# fixed.net
KiCad netlist of a schematic drawn in EAGLE
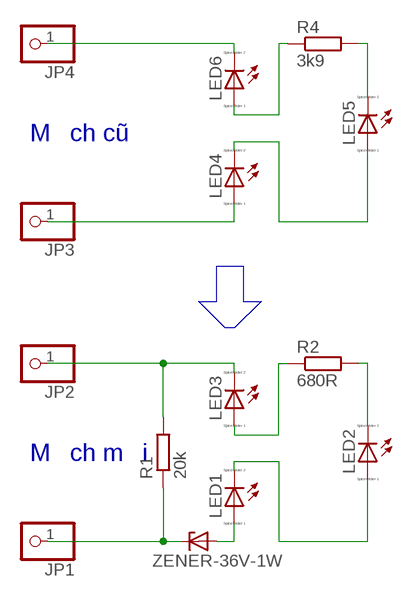
[diagram p0: schematic, sheet 1]

(export (version "E")
  (design (tool "Eeschema 10.0.6"))
  (components
    (comp (ref "JP1")
      (value "PINHD-1X1")
      (footprint "eagle-import:1X01")
      (libsource (lib "eagle-import") (part "PINHD-1X1"))
    )
    (comp (ref "JP2")
      (value "PINHD-1X1")
      (footprint "eagle-import:1X01")
      (libsource (lib "eagle-import") (part "PINHD-1X1"))
    )
    (comp (ref "JP3")
      (value "PINHD-1X1")
      (footprint "eagle-import:1X01")
      (libsource (lib "eagle-import") (part "PINHD-1X1"))
    )
    (comp (ref "JP4")
      (value "PINHD-1X1")
      (footprint "eagle-import:1X01")
      (libsource (lib "eagle-import") (part "PINHD-1X1"))
    )
    (comp (ref "LED1")
      (value "LED_E")
      (footprint "eagle-import:LED_1206")
      (libsource (lib "eagle-import") (part "LED_E"))
    )
    (comp (ref "LED2")
      (value "LED_E")
      (footprint "eagle-import:LED_1206")
      (libsource (lib "eagle-import") (part "LED_E"))
    )
    (comp (ref "LED3")
      (value "LED_E")
      (footprint "eagle-import:LED_1206")
      (libsource (lib "eagle-import") (part "LED_E"))
    )
    (comp (ref "LED4")
      (value "LED_E")
      (footprint "eagle-import:LED_1206")
      (libsource (lib "eagle-import") (part "LED_E"))
    )
    (comp (ref "LED5")
      (value "LED_E")
      (footprint "eagle-import:LED_1206")
      (libsource (lib "eagle-import") (part "LED_E"))
    )
    (comp (ref "LED6")
      (value "LED_E")
      (footprint "eagle-import:LED_1206")
      (libsource (lib "eagle-import") (part "LED_E"))
    )
    (comp (ref "R1")
      (value "20k")
      (footprint "eagle-import:0204_7")
      (libsource (lib "eagle-import") (part "R-EU_0204/7"))
    )
    (comp (ref "R2")
      (value "680R")
      (footprint "eagle-import:0204_7")
      (libsource (lib "eagle-import") (part "R-EU_0204/7"))
    )
    (comp (ref "R4")
      (value "3k9")
      (footprint "eagle-import:0204_7")
      (libsource (lib "eagle-import") (part "R-EU_0204/7"))
    )
    (comp (ref "ZENER-36V-1W")
      (value "1N4728")
      (footprint "eagle-import:DO41Z10")
      (libsource (lib "eagle-import") (part "1N4728"))
    )
  )
  (nets
    (net (code "1") (name "Net-(JP1-Pad1)") (class "Default")
      (node (ref "JP1") (pin "1") (pinfunction "1_1") (pintype "passive"))
      (node (ref "R1") (pin "1") (pinfunction "1_1") (pintype "passive"))
      (node (ref "ZENER-36V-1W") (pin "C") (pinfunction "C_C") (pintype "passive"))
    )
    (net (code "2") (name "Net-(JP2-Pad1)") (class "Default")
      (node (ref "JP2") (pin "1") (pinfunction "1_1") (pintype "passive"))
      (node (ref "LED3") (pin "C") (pinfunction "C_C") (pintype "passive"))
      (node (ref "R1") (pin "2") (pinfunction "2_2") (pintype "passive"))
    )
    (net (code "3") (name "Net-(JP3-Pad1)") (class "Default")
      (node (ref "JP3") (pin "1") (pinfunction "1_1") (pintype "passive"))
      (node (ref "LED4") (pin "A") (pinfunction "A_A") (pintype "passive"))
    )
    (net (code "4") (name "Net-(JP4-Pad1)") (class "Default")
      (node (ref "JP4") (pin "1") (pinfunction "1_1") (pintype "passive"))
      (node (ref "LED6") (pin "C") (pinfunction "C_C") (pintype "passive"))
    )
    (net (code "5") (name "Net-(LED1-PadA)") (class "Default")
      (node (ref "LED1") (pin "A") (pinfunction "A_A") (pintype "passive"))
      (node (ref "ZENER-36V-1W") (pin "A") (pinfunction "A_A") (pintype "passive"))
    )
    (net (code "6") (name "Net-(LED1-PadC)") (class "Default")
      (node (ref "LED1") (pin "C") (pinfunction "C_C") (pintype "passive"))
      (node (ref "LED2") (pin "A") (pinfunction "A_A") (pintype "passive"))
    )
    (net (code "7") (name "Net-(LED2-PadC)") (class "Default")
      (node (ref "LED2") (pin "C") (pinfunction "C_C") (pintype "passive"))
      (node (ref "R2") (pin "2") (pinfunction "2_2") (pintype "passive"))
    )
    (net (code "8") (name "Net-(LED3-PadA)") (class "Default")
      (node (ref "LED3") (pin "A") (pinfunction "A_A") (pintype "passive"))
      (node (ref "R2") (pin "1") (pinfunction "1_1") (pintype "passive"))
    )
    (net (code "9") (name "Net-(LED4-PadC)") (class "Default")
      (node (ref "LED4") (pin "C") (pinfunction "C_C") (pintype "passive"))
      (node (ref "LED5") (pin "A") (pinfunction "A_A") (pintype "passive"))
    )
    (net (code "10") (name "Net-(LED5-PadC)") (class "Default")
      (node (ref "LED5") (pin "C") (pinfunction "C_C") (pintype "passive"))
      (node (ref "R4") (pin "2") (pinfunction "2_2") (pintype "passive"))
    )
    (net (code "11") (name "Net-(LED6-PadA)") (class "Default")
      (node (ref "LED6") (pin "A") (pinfunction "A_A") (pintype "passive"))
      (node (ref "R4") (pin "1") (pinfunction "1_1") (pintype "passive"))
    )
  )
)
